# do.net
KiCad netlist of a schematic drawn in Altium Designer
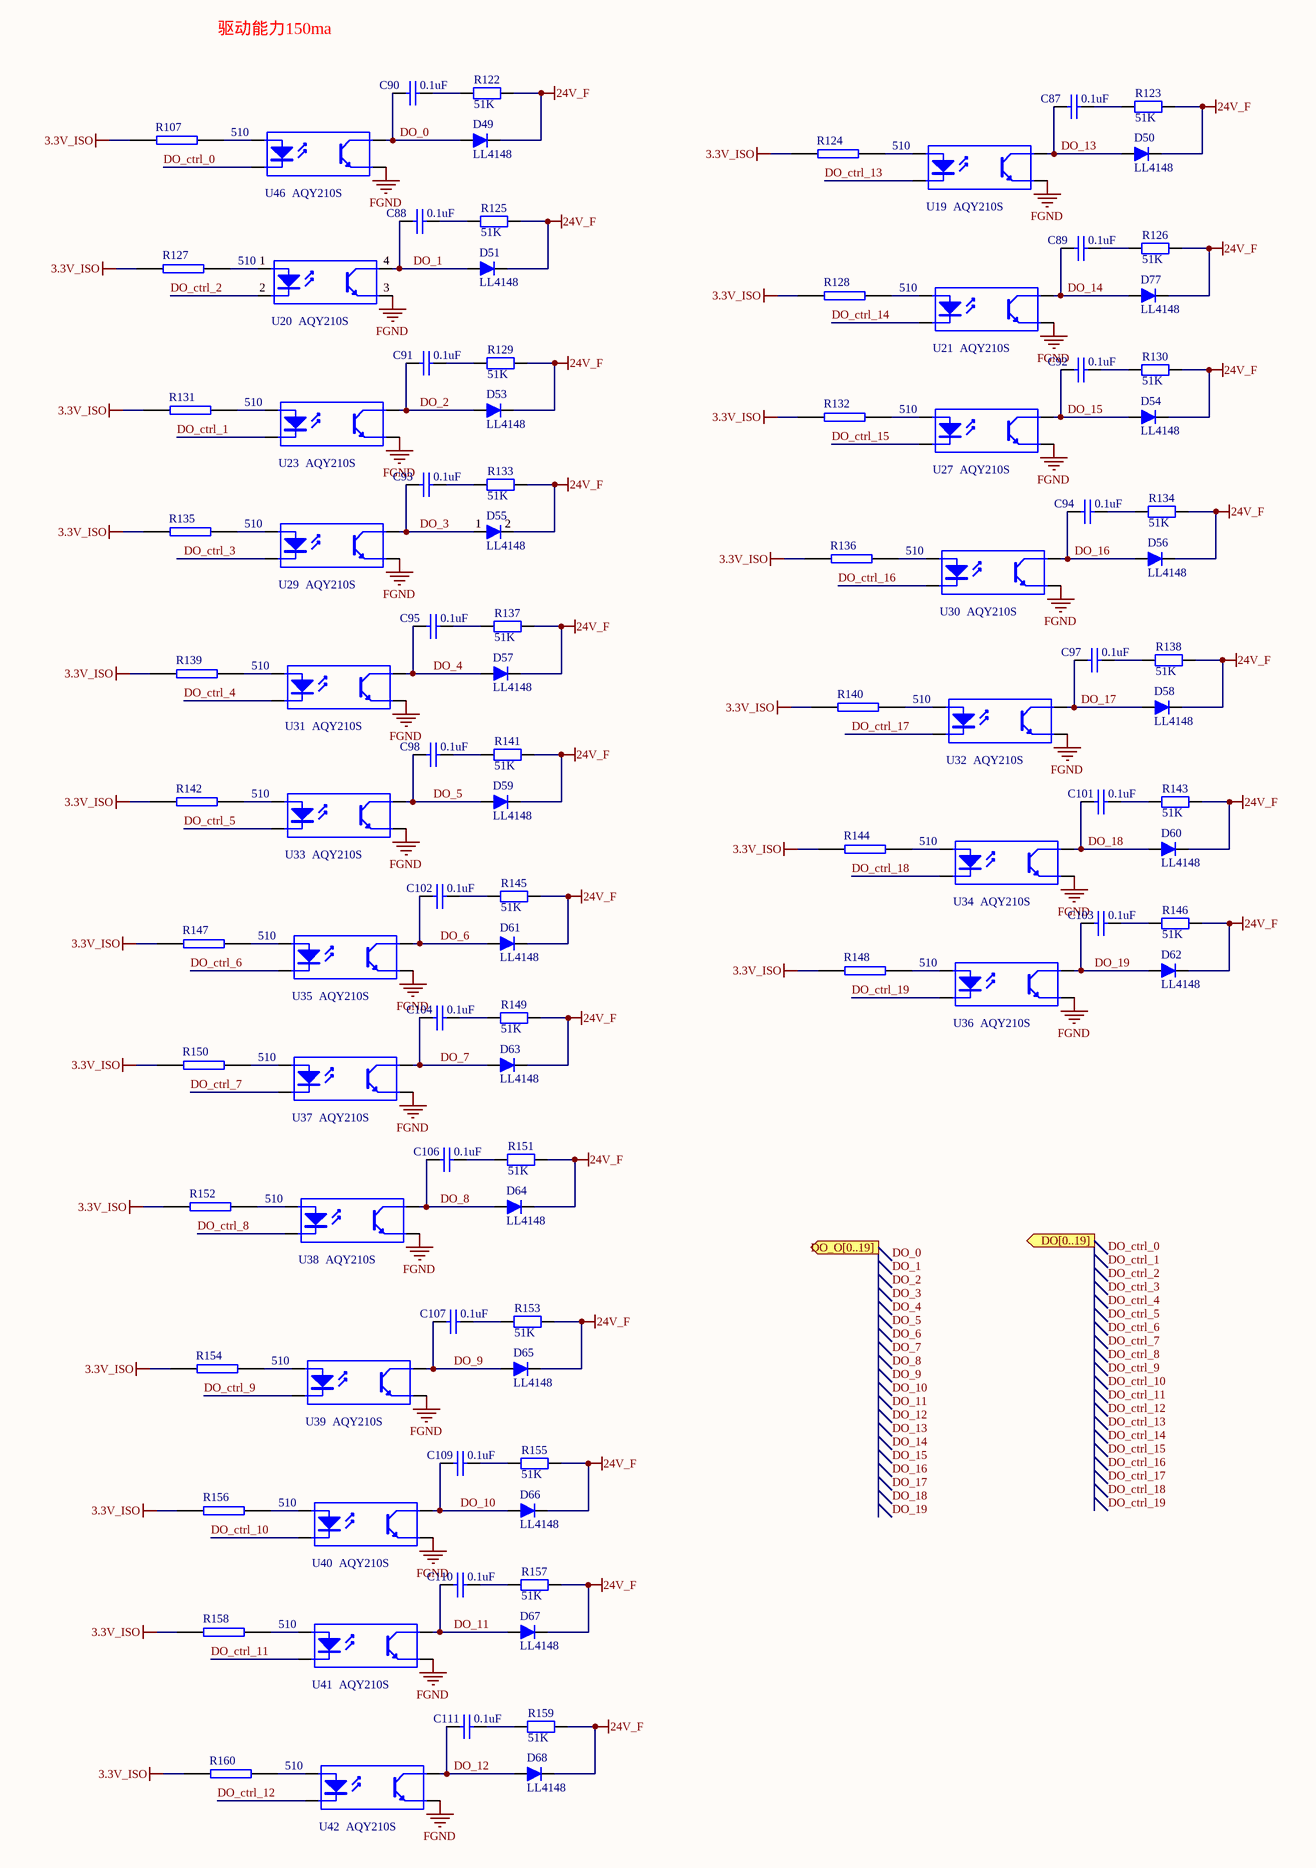
[diagram p0: do.SchDoc]

(export (version "E")
  (design (tool "Eeschema 10.0.6"))
  (components
    (comp (ref "C87")
      (value "0.1uF")
      (footprint "0603C")
      (description "Capacitor")
      (libsource (lib "*") (part "CAP"))
    )
    (comp (ref "C88")
      (value "0.1uF")
      (footprint "0603C")
      (description "Capacitor")
      (libsource (lib "*") (part "CAP"))
    )
    (comp (ref "C89")
      (value "0.1uF")
      (footprint "0603C")
      (description "Capacitor")
      (libsource (lib "*") (part "CAP"))
    )
    (comp (ref "C90")
      (value "0.1uF")
      (footprint "0603C")
      (description "Capacitor")
      (libsource (lib "*") (part "CAP"))
    )
    (comp (ref "C91")
      (value "0.1uF")
      (footprint "0603C")
      (description "Capacitor")
      (libsource (lib "*") (part "CAP"))
    )
    (comp (ref "C92")
      (value "0.1uF")
      (footprint "0603C")
      (description "Capacitor")
      (libsource (lib "*") (part "CAP"))
    )
    (comp (ref "C93")
      (value "0.1uF")
      (footprint "0603C")
      (description "Capacitor")
      (libsource (lib "*") (part "CAP"))
    )
    (comp (ref "C94")
      (value "0.1uF")
      (footprint "0603C")
      (description "Capacitor")
      (libsource (lib "*") (part "CAP"))
    )
    (comp (ref "C95")
      (value "0.1uF")
      (footprint "0603C")
      (description "Capacitor")
      (libsource (lib "*") (part "CAP"))
    )
    (comp (ref "C97")
      (value "0.1uF")
      (footprint "0603C")
      (description "Capacitor")
      (libsource (lib "*") (part "CAP"))
    )
    (comp (ref "C98")
      (value "0.1uF")
      (footprint "0603C")
      (description "Capacitor")
      (libsource (lib "*") (part "CAP"))
    )
    (comp (ref "C101")
      (value "0.1uF")
      (footprint "0603C")
      (description "Capacitor")
      (libsource (lib "*") (part "CAP"))
    )
    (comp (ref "C102")
      (value "0.1uF")
      (footprint "0603C")
      (description "Capacitor")
      (libsource (lib "*") (part "CAP"))
    )
    (comp (ref "C103")
      (value "0.1uF")
      (footprint "0603C")
      (description "Capacitor")
      (libsource (lib "*") (part "CAP"))
    )
    (comp (ref "C104")
      (value "0.1uF")
      (footprint "0603C")
      (description "Capacitor")
      (libsource (lib "*") (part "CAP"))
    )
    (comp (ref "C106")
      (value "0.1uF")
      (footprint "0603C")
      (description "Capacitor")
      (libsource (lib "*") (part "CAP"))
    )
    (comp (ref "C107")
      (value "0.1uF")
      (footprint "0603C")
      (description "Capacitor")
      (libsource (lib "*") (part "CAP"))
    )
    (comp (ref "C109")
      (value "0.1uF")
      (footprint "0603C")
      (description "Capacitor")
      (libsource (lib "*") (part "CAP"))
    )
    (comp (ref "C110")
      (value "0.1uF")
      (footprint "0603C")
      (description "Capacitor")
      (libsource (lib "*") (part "CAP"))
    )
    (comp (ref "C111")
      (value "0.1uF")
      (footprint "0603C")
      (description "Capacitor")
      (libsource (lib "*") (part "CAP"))
    )
    (comp (ref "D49")
      (value "LL4148")
      (footprint "DO-213AB/LL34/MiniMELF")
      (description "VISHAY,LL4148,圆柱体MiniMELF100V/2A,ROHS")
      (libsource (lib "controller_V1.1") (part "LL4148"))
    )
    (comp (ref "D50")
      (value "LL4148")
      (footprint "DO-213AB/LL34/MiniMELF")
      (description "VISHAY,LL4148,圆柱体MiniMELF100V/2A,ROHS")
      (libsource (lib "controller_V1.1") (part "LL4148"))
    )
    (comp (ref "D51")
      (value "LL4148")
      (footprint "DO-213AB/LL34/MiniMELF")
      (description "VISHAY,LL4148,圆柱体MiniMELF100V/2A,ROHS")
      (libsource (lib "controller_V1.1") (part "LL4148"))
    )
    (comp (ref "D53")
      (value "LL4148")
      (footprint "DO-213AB/LL34/MiniMELF")
      (description "VISHAY,LL4148,圆柱体MiniMELF100V/2A,ROHS")
      (libsource (lib "controller_V1.1") (part "LL4148"))
    )
    (comp (ref "D54")
      (value "LL4148")
      (footprint "DO-213AB/LL34/MiniMELF")
      (description "VISHAY,LL4148,圆柱体MiniMELF100V/2A,ROHS")
      (libsource (lib "controller_V1.1") (part "LL4148"))
    )
    (comp (ref "D55")
      (value "LL4148")
      (footprint "DO-213AB/LL34/MiniMELF")
      (description "VISHAY,LL4148,圆柱体MiniMELF100V/2A,ROHS")
      (libsource (lib "") (part "LL4148_1"))
    )
    (comp (ref "D56")
      (value "LL4148")
      (footprint "DO-213AB/LL34/MiniMELF")
      (description "VISHAY,LL4148,圆柱体MiniMELF100V/2A,ROHS")
      (libsource (lib "controller_V1.1") (part "LL4148"))
    )
    (comp (ref "D57")
      (value "LL4148")
      (footprint "DO-213AB/LL34/MiniMELF")
      (description "VISHAY,LL4148,圆柱体MiniMELF100V/2A,ROHS")
      (libsource (lib "controller_V1.1") (part "LL4148"))
    )
    (comp (ref "D58")
      (value "LL4148")
      (footprint "DO-213AB/LL34/MiniMELF")
      (description "VISHAY,LL4148,圆柱体MiniMELF100V/2A,ROHS")
      (libsource (lib "controller_V1.1") (part "LL4148"))
    )
    (comp (ref "D59")
      (value "LL4148")
      (footprint "DO-213AB/LL34/MiniMELF")
      (description "VISHAY,LL4148,圆柱体MiniMELF100V/2A,ROHS")
      (libsource (lib "controller_V1.1") (part "LL4148"))
    )
    (comp (ref "D60")
      (value "LL4148")
      (footprint "DO-213AB/LL34/MiniMELF")
      (description "VISHAY,LL4148,圆柱体MiniMELF100V/2A,ROHS")
      (libsource (lib "controller_V1.1") (part "LL4148"))
    )
    (comp (ref "D61")
      (value "LL4148")
      (footprint "DO-213AB/LL34/MiniMELF")
      (description "VISHAY,LL4148,圆柱体MiniMELF100V/2A,ROHS")
      (libsource (lib "controller_V1.1") (part "LL4148"))
    )
    (comp (ref "D62")
      (value "LL4148")
      (footprint "DO-213AB/LL34/MiniMELF")
      (description "VISHAY,LL4148,圆柱体MiniMELF100V/2A,ROHS")
      (libsource (lib "controller_V1.1") (part "LL4148"))
    )
    (comp (ref "D63")
      (value "LL4148")
      (footprint "DO-213AB/LL34/MiniMELF")
      (description "VISHAY,LL4148,圆柱体MiniMELF100V/2A,ROHS")
      (libsource (lib "controller_V1.1") (part "LL4148"))
    )
    (comp (ref "D64")
      (value "LL4148")
      (footprint "DO-213AB/LL34/MiniMELF")
      (description "VISHAY,LL4148,圆柱体MiniMELF100V/2A,ROHS")
      (libsource (lib "controller_V1.1") (part "LL4148"))
    )
    (comp (ref "D65")
      (value "LL4148")
      (footprint "DO-213AB/LL34/MiniMELF")
      (description "VISHAY,LL4148,圆柱体MiniMELF100V/2A,ROHS")
      (libsource (lib "controller_V1.1") (part "LL4148"))
    )
    (comp (ref "D66")
      (value "LL4148")
      (footprint "DO-213AB/LL34/MiniMELF")
      (description "VISHAY,LL4148,圆柱体MiniMELF100V/2A,ROHS")
      (libsource (lib "controller_V1.1") (part "LL4148"))
    )
    (comp (ref "D67")
      (value "LL4148")
      (footprint "DO-213AB/LL34/MiniMELF")
      (description "VISHAY,LL4148,圆柱体MiniMELF100V/2A,ROHS")
      (libsource (lib "controller_V1.1") (part "LL4148"))
    )
    (comp (ref "D68")
      (value "LL4148")
      (footprint "DO-213AB/LL34/MiniMELF")
      (description "VISHAY,LL4148,圆柱体MiniMELF100V/2A,ROHS")
      (libsource (lib "controller_V1.1") (part "LL4148"))
    )
    (comp (ref "D77")
      (value "LL4148")
      (footprint "DO-213AB/LL34/MiniMELF")
      (description "VISHAY,LL4148,圆柱体MiniMELF100V/2A,ROHS")
      (libsource (lib "controller_V1.1") (part "LL4148"))
    )
    (comp (ref "R107") (value "510") (footprint "0603R") (libsource (lib "*") (part "RES2")))
    (comp (ref "R122") (value "51K") (footprint "0603R") (libsource (lib "MQlibrary") (part "Res0805M")))
    (comp (ref "R123") (value "51K") (footprint "0603R") (libsource (lib "MQlibrary") (part "Res0805M")))
    (comp (ref "R124") (value "510") (footprint "0603R") (libsource (lib "*") (part "RES2")))
    (comp (ref "R125") (value "51K") (footprint "0603R") (libsource (lib "MQlibrary") (part "Res0805M")))
    (comp (ref "R126") (value "51K") (footprint "0603R") (libsource (lib "MQlibrary") (part "Res0805M")))
    (comp (ref "R127") (value "510") (footprint "0603R") (libsource (lib "*") (part "RES2")))
    (comp (ref "R128") (value "510") (footprint "0603R") (libsource (lib "*") (part "RES2")))
    (comp (ref "R129") (value "51K") (footprint "0603R") (libsource (lib "MQlibrary") (part "Res0805M")))
    (comp (ref "R130") (value "51K") (footprint "0603R") (libsource (lib "MQlibrary") (part "Res0805M")))
    (comp (ref "R131") (value "510") (footprint "0603R") (libsource (lib "*") (part "RES2")))
    (comp (ref "R132") (value "510") (footprint "0603R") (libsource (lib "*") (part "RES2")))
    (comp (ref "R133") (value "51K") (footprint "0603R") (libsource (lib "MQlibrary") (part "Res0805M")))
    (comp (ref "R134") (value "51K") (footprint "0603R") (libsource (lib "MQlibrary") (part "Res0805M")))
    (comp (ref "R135") (value "510") (footprint "0603R") (libsource (lib "*") (part "RES2")))
    (comp (ref "R136") (value "510") (footprint "0603R") (libsource (lib "*") (part "RES2")))
    (comp (ref "R137") (value "51K") (footprint "0603R") (libsource (lib "MQlibrary") (part "Res0805M")))
    (comp (ref "R138") (value "51K") (footprint "0603R") (libsource (lib "MQlibrary") (part "Res0805M")))
    (comp (ref "R139") (value "510") (footprint "0603R") (libsource (lib "*") (part "RES2")))
    (comp (ref "R140") (value "510") (footprint "0603R") (libsource (lib "*") (part "RES2")))
    (comp (ref "R141") (value "51K") (footprint "0603R") (libsource (lib "MQlibrary") (part "Res0805M")))
    (comp (ref "R142") (value "510") (footprint "0603R") (libsource (lib "*") (part "RES2")))
    (comp (ref "R143") (value "51K") (footprint "0603R") (libsource (lib "MQlibrary") (part "Res0805M")))
    (comp (ref "R144") (value "510") (footprint "0603R") (libsource (lib "*") (part "RES2")))
    (comp (ref "R145") (value "51K") (footprint "0603R") (libsource (lib "MQlibrary") (part "Res0805M")))
    (comp (ref "R146") (value "51K") (footprint "0603R") (libsource (lib "MQlibrary") (part "Res0805M")))
    (comp (ref "R147") (value "510") (footprint "0603R") (libsource (lib "*") (part "RES2")))
    (comp (ref "R148") (value "510") (footprint "0603R") (libsource (lib "*") (part "RES2")))
    (comp (ref "R149") (value "51K") (footprint "0603R") (libsource (lib "MQlibrary") (part "Res0805M")))
    (comp (ref "R150") (value "510") (footprint "0603R") (libsource (lib "*") (part "RES2")))
    (comp (ref "R151") (value "51K") (footprint "0603R") (libsource (lib "MQlibrary") (part "Res0805M")))
    (comp (ref "R152") (value "510") (footprint "0603R") (libsource (lib "*") (part "RES2")))
    (comp (ref "R153") (value "51K") (footprint "0603R") (libsource (lib "MQlibrary") (part "Res0805M")))
    (comp (ref "R154") (value "510") (footprint "0603R") (libsource (lib "*") (part "RES2")))
    (comp (ref "R155") (value "51K") (footprint "0603R") (libsource (lib "MQlibrary") (part "Res0805M")))
    (comp (ref "R156") (value "510") (footprint "0603R") (libsource (lib "*") (part "RES2")))
    (comp (ref "R157") (value "51K") (footprint "0603R") (libsource (lib "MQlibrary") (part "Res0805M")))
    (comp (ref "R158") (value "510") (footprint "0603R") (libsource (lib "*") (part "RES2")))
    (comp (ref "R159") (value "51K") (footprint "0603R") (libsource (lib "MQlibrary") (part "Res0805M")))
    (comp (ref "R160") (value "510") (footprint "0603R") (libsource (lib "*") (part "RES2")))
    (comp (ref "U19")
      (value "AQY210S")
      (footprint "sop4")
      (description "4-Pin Phototransistor Optocoupler")
      (fields (field (name "PUBLISHER") "Altium Limited"))
      (libsource (lib "Miscellaneous Devices") (part "Optoisolator1"))
    )
    (comp (ref "U20")
      (value "AQY210S")
      (footprint "sop4")
      (description "4-Pin Phototransistor Optocoupler")
      (fields (field (name "PUBLISHER") "Altium Limited"))
      (libsource (lib "") (part "Optoisolator1_1"))
    )
    (comp (ref "U21")
      (value "AQY210S")
      (footprint "sop4")
      (description "4-Pin Phototransistor Optocoupler")
      (fields (field (name "PUBLISHER") "Altium Limited"))
      (libsource (lib "Miscellaneous Devices") (part "Optoisolator1"))
    )
    (comp (ref "U23")
      (value "AQY210S")
      (footprint "sop4")
      (description "4-Pin Phototransistor Optocoupler")
      (fields (field (name "PUBLISHER") "Altium Limited"))
      (libsource (lib "Miscellaneous Devices") (part "Optoisolator1"))
    )
    (comp (ref "U27")
      (value "AQY210S")
      (footprint "sop4")
      (description "4-Pin Phototransistor Optocoupler")
      (fields (field (name "PUBLISHER") "Altium Limited"))
      (libsource (lib "Miscellaneous Devices") (part "Optoisolator1"))
    )
    (comp (ref "U29")
      (value "AQY210S")
      (footprint "sop4")
      (description "4-Pin Phototransistor Optocoupler")
      (fields (field (name "PUBLISHER") "Altium Limited"))
      (libsource (lib "Miscellaneous Devices") (part "Optoisolator1"))
    )
    (comp (ref "U30")
      (value "AQY210S")
      (footprint "sop4")
      (description "4-Pin Phototransistor Optocoupler")
      (fields (field (name "PUBLISHER") "Altium Limited"))
      (libsource (lib "Miscellaneous Devices") (part "Optoisolator1"))
    )
    (comp (ref "U31")
      (value "AQY210S")
      (footprint "sop4")
      (description "4-Pin Phototransistor Optocoupler")
      (fields (field (name "PUBLISHER") "Altium Limited"))
      (libsource (lib "Miscellaneous Devices") (part "Optoisolator1"))
    )
    (comp (ref "U32")
      (value "AQY210S")
      (footprint "sop4")
      (description "4-Pin Phototransistor Optocoupler")
      (fields (field (name "PUBLISHER") "Altium Limited"))
      (libsource (lib "Miscellaneous Devices") (part "Optoisolator1"))
    )
    (comp (ref "U33")
      (value "AQY210S")
      (footprint "sop4")
      (description "4-Pin Phototransistor Optocoupler")
      (fields (field (name "PUBLISHER") "Altium Limited"))
      (libsource (lib "Miscellaneous Devices") (part "Optoisolator1"))
    )
    (comp (ref "U34")
      (value "AQY210S")
      (footprint "sop4")
      (description "4-Pin Phototransistor Optocoupler")
      (fields (field (name "PUBLISHER") "Altium Limited"))
      (libsource (lib "Miscellaneous Devices") (part "Optoisolator1"))
    )
    (comp (ref "U35")
      (value "AQY210S")
      (footprint "sop4")
      (description "4-Pin Phototransistor Optocoupler")
      (fields (field (name "PUBLISHER") "Altium Limited"))
      (libsource (lib "Miscellaneous Devices") (part "Optoisolator1"))
    )
    (comp (ref "U36")
      (value "AQY210S")
      (footprint "sop4")
      (description "4-Pin Phototransistor Optocoupler")
      (fields (field (name "PUBLISHER") "Altium Limited"))
      (libsource (lib "Miscellaneous Devices") (part "Optoisolator1"))
    )
    (comp (ref "U37")
      (value "AQY210S")
      (footprint "sop4")
      (description "4-Pin Phototransistor Optocoupler")
      (fields (field (name "PUBLISHER") "Altium Limited"))
      (libsource (lib "Miscellaneous Devices") (part "Optoisolator1"))
    )
    (comp (ref "U38")
      (value "AQY210S")
      (footprint "sop4")
      (description "4-Pin Phototransistor Optocoupler")
      (fields (field (name "PUBLISHER") "Altium Limited"))
      (libsource (lib "Miscellaneous Devices") (part "Optoisolator1"))
    )
    (comp (ref "U39")
      (value "AQY210S")
      (footprint "sop4")
      (description "4-Pin Phototransistor Optocoupler")
      (fields (field (name "PUBLISHER") "Altium Limited"))
      (libsource (lib "Miscellaneous Devices") (part "Optoisolator1"))
    )
    (comp (ref "U40")
      (value "AQY210S")
      (footprint "sop4")
      (description "4-Pin Phototransistor Optocoupler")
      (fields (field (name "PUBLISHER") "Altium Limited"))
      (libsource (lib "Miscellaneous Devices") (part "Optoisolator1"))
    )
    (comp (ref "U41")
      (value "AQY210S")
      (footprint "sop4")
      (description "4-Pin Phototransistor Optocoupler")
      (fields (field (name "PUBLISHER") "Altium Limited"))
      (libsource (lib "Miscellaneous Devices") (part "Optoisolator1"))
    )
    (comp (ref "U42")
      (value "AQY210S")
      (footprint "sop4")
      (description "4-Pin Phototransistor Optocoupler")
      (fields (field (name "PUBLISHER") "Altium Limited"))
      (libsource (lib "Miscellaneous Devices") (part "Optoisolator1"))
    )
    (comp (ref "U46")
      (value "AQY210S")
      (footprint "sop4")
      (description "4-Pin Phototransistor Optocoupler")
      (fields (field (name "PUBLISHER") "Altium Limited"))
      (libsource (lib "Miscellaneous Devices") (part "Optoisolator1"))
    )
  )
  (nets
    (net (code "42") (name "/DO_0") (class "Default")
      (node (ref "C90") (pin "1") (pinfunction "1_1") (pintype "passive"))
      (node (ref "D49") (pin "1") (pinfunction "A_1") (pintype "passive"))
      (node (ref "U46") (pin "4") (pinfunction "C_4") (pintype "passive"))
    )
    (net (code "43") (name "/DO_1") (class "Default")
      (node (ref "C88") (pin "1") (pinfunction "1_1") (pintype "passive"))
      (node (ref "D51") (pin "1") (pinfunction "A_1") (pintype "passive"))
      (node (ref "U20") (pin "4") (pinfunction "C_4") (pintype "passive"))
    )
    (net (code "44") (name "/DO_2") (class "Default")
      (node (ref "C91") (pin "1") (pinfunction "1_1") (pintype "passive"))
      (node (ref "D53") (pin "1") (pinfunction "A_1") (pintype "passive"))
      (node (ref "U23") (pin "4") (pinfunction "C_4") (pintype "passive"))
    )
    (net (code "45") (name "/DO_3") (class "Default")
      (node (ref "C93") (pin "1") (pinfunction "1_1") (pintype "passive"))
      (node (ref "D55") (pin "1") (pinfunction "A_1") (pintype "passive"))
      (node (ref "U29") (pin "4") (pinfunction "C_4") (pintype "passive"))
    )
    (net (code "46") (name "/DO_4") (class "Default")
      (node (ref "C95") (pin "1") (pinfunction "1_1") (pintype "passive"))
      (node (ref "D57") (pin "1") (pinfunction "A_1") (pintype "passive"))
      (node (ref "U31") (pin "4") (pinfunction "C_4") (pintype "passive"))
    )
    (net (code "47") (name "/DO_5") (class "Default")
      (node (ref "C98") (pin "1") (pinfunction "1_1") (pintype "passive"))
      (node (ref "D59") (pin "1") (pinfunction "A_1") (pintype "passive"))
      (node (ref "U33") (pin "4") (pinfunction "C_4") (pintype "passive"))
    )
    (net (code "48") (name "/DO_6") (class "Default")
      (node (ref "C102") (pin "1") (pinfunction "1_1") (pintype "passive"))
      (node (ref "D61") (pin "1") (pinfunction "A_1") (pintype "passive"))
      (node (ref "U35") (pin "4") (pinfunction "C_4") (pintype "passive"))
    )
    (net (code "49") (name "/DO_7") (class "Default")
      (node (ref "C104") (pin "1") (pinfunction "1_1") (pintype "passive"))
      (node (ref "D63") (pin "1") (pinfunction "A_1") (pintype "passive"))
      (node (ref "U37") (pin "4") (pinfunction "C_4") (pintype "passive"))
    )
    (net (code "50") (name "/DO_8") (class "Default")
      (node (ref "C106") (pin "1") (pinfunction "1_1") (pintype "passive"))
      (node (ref "D64") (pin "1") (pinfunction "A_1") (pintype "passive"))
      (node (ref "U38") (pin "4") (pinfunction "C_4") (pintype "passive"))
    )
    (net (code "51") (name "/DO_9") (class "Default")
      (node (ref "C107") (pin "1") (pinfunction "1_1") (pintype "passive"))
      (node (ref "D65") (pin "1") (pinfunction "A_1") (pintype "passive"))
      (node (ref "U39") (pin "4") (pinfunction "C_4") (pintype "passive"))
    )
    (net (code "52") (name "/DO_10") (class "Default")
      (node (ref "C109") (pin "1") (pinfunction "1_1") (pintype "passive"))
      (node (ref "D66") (pin "1") (pinfunction "A_1") (pintype "passive"))
      (node (ref "U40") (pin "4") (pinfunction "C_4") (pintype "passive"))
    )
    (net (code "53") (name "/DO_11") (class "Default")
      (node (ref "C110") (pin "1") (pinfunction "1_1") (pintype "passive"))
      (node (ref "D67") (pin "1") (pinfunction "A_1") (pintype "passive"))
      (node (ref "U41") (pin "4") (pinfunction "C_4") (pintype "passive"))
    )
    (net (code "54") (name "/DO_12") (class "Default")
      (node (ref "C111") (pin "1") (pinfunction "1_1") (pintype "passive"))
      (node (ref "D68") (pin "1") (pinfunction "A_1") (pintype "passive"))
      (node (ref "U42") (pin "4") (pinfunction "C_4") (pintype "passive"))
    )
    (net (code "55") (name "/DO_13") (class "Default")
      (node (ref "C87") (pin "1") (pinfunction "1_1") (pintype "passive"))
      (node (ref "D50") (pin "1") (pinfunction "A_1") (pintype "passive"))
      (node (ref "U19") (pin "4") (pinfunction "C_4") (pintype "passive"))
    )
    (net (code "56") (name "/DO_14") (class "Default")
      (node (ref "C89") (pin "1") (pinfunction "1_1") (pintype "passive"))
      (node (ref "D77") (pin "1") (pinfunction "A_1") (pintype "passive"))
      (node (ref "U21") (pin "4") (pinfunction "C_4") (pintype "passive"))
    )
    (net (code "57") (name "/DO_15") (class "Default")
      (node (ref "C92") (pin "1") (pinfunction "1_1") (pintype "passive"))
      (node (ref "D54") (pin "1") (pinfunction "A_1") (pintype "passive"))
      (node (ref "U27") (pin "4") (pinfunction "C_4") (pintype "passive"))
    )
    (net (code "58") (name "/DO_16") (class "Default")
      (node (ref "C94") (pin "1") (pinfunction "1_1") (pintype "passive"))
      (node (ref "D56") (pin "1") (pinfunction "A_1") (pintype "passive"))
      (node (ref "U30") (pin "4") (pinfunction "C_4") (pintype "passive"))
    )
    (net (code "59") (name "/DO_17") (class "Default")
      (node (ref "C97") (pin "1") (pinfunction "1_1") (pintype "passive"))
      (node (ref "D58") (pin "1") (pinfunction "A_1") (pintype "passive"))
      (node (ref "U32") (pin "4") (pinfunction "C_4") (pintype "passive"))
    )
    (net (code "60") (name "/DO_18") (class "Default")
      (node (ref "C101") (pin "1") (pinfunction "1_1") (pintype "passive"))
      (node (ref "D60") (pin "1") (pinfunction "A_1") (pintype "passive"))
      (node (ref "U34") (pin "4") (pinfunction "C_4") (pintype "passive"))
    )
    (net (code "61") (name "/DO_19") (class "Default")
      (node (ref "C103") (pin "1") (pinfunction "1_1") (pintype "passive"))
      (node (ref "D62") (pin "1") (pinfunction "A_1") (pintype "passive"))
      (node (ref "U36") (pin "4") (pinfunction "C_4") (pintype "passive"))
    )
    (net (code "63") (name "/DO_ctrl_0") (class "Default")
      (node (ref "U46") (pin "2") (pinfunction "K_2") (pintype "passive"))
    )
    (net (code "64") (name "/DO_ctrl_1") (class "Default")
      (node (ref "U23") (pin "2") (pinfunction "K_2") (pintype "passive"))
    )
    (net (code "65") (name "/DO_ctrl_2") (class "Default")
      (node (ref "U20") (pin "2") (pinfunction "K_2") (pintype "passive"))
    )
    (net (code "66") (name "/DO_ctrl_3") (class "Default")
      (node (ref "U29") (pin "2") (pinfunction "K_2") (pintype "passive"))
    )
    (net (code "67") (name "/DO_ctrl_4") (class "Default")
      (node (ref "U31") (pin "2") (pinfunction "K_2") (pintype "passive"))
    )
    (net (code "68") (name "/DO_ctrl_5") (class "Default")
      (node (ref "U33") (pin "2") (pinfunction "K_2") (pintype "passive"))
    )
    (net (code "69") (name "/DO_ctrl_6") (class "Default")
      (node (ref "U35") (pin "2") (pinfunction "K_2") (pintype "passive"))
    )
    (net (code "70") (name "/DO_ctrl_7") (class "Default")
      (node (ref "U37") (pin "2") (pinfunction "K_2") (pintype "passive"))
    )
    (net (code "71") (name "/DO_ctrl_8") (class "Default")
      (node (ref "U38") (pin "2") (pinfunction "K_2") (pintype "passive"))
    )
    (net (code "72") (name "/DO_ctrl_9") (class "Default")
      (node (ref "U39") (pin "2") (pinfunction "K_2") (pintype "passive"))
    )
    (net (code "73") (name "/DO_ctrl_10") (class "Default")
      (node (ref "U40") (pin "2") (pinfunction "K_2") (pintype "passive"))
    )
    (net (code "74") (name "/DO_ctrl_11") (class "Default")
      (node (ref "U41") (pin "2") (pinfunction "K_2") (pintype "passive"))
    )
    (net (code "75") (name "/DO_ctrl_12") (class "Default")
      (node (ref "U42") (pin "2") (pinfunction "K_2") (pintype "passive"))
    )
    (net (code "76") (name "/DO_ctrl_13") (class "Default")
      (node (ref "U19") (pin "2") (pinfunction "K_2") (pintype "passive"))
    )
    (net (code "77") (name "/DO_ctrl_14") (class "Default")
      (node (ref "U21") (pin "2") (pinfunction "K_2") (pintype "passive"))
    )
    (net (code "78") (name "/DO_ctrl_15") (class "Default")
      (node (ref "U27") (pin "2") (pinfunction "K_2") (pintype "passive"))
    )
    (net (code "79") (name "/DO_ctrl_16") (class "Default")
      (node (ref "U30") (pin "2") (pinfunction "K_2") (pintype "passive"))
    )
    (net (code "80") (name "/DO_ctrl_17") (class "Default")
      (node (ref "U32") (pin "2") (pinfunction "K_2") (pintype "passive"))
    )
    (net (code "81") (name "/DO_ctrl_18") (class "Default")
      (node (ref "U34") (pin "2") (pinfunction "K_2") (pintype "passive"))
    )
    (net (code "82") (name "/DO_ctrl_19") (class "Default")
      (node (ref "U36") (pin "2") (pinfunction "K_2") (pintype "passive"))
    )
    (net (code "83") (name "3.3V_ISO") (class "Default")
      (node (ref "R107") (pin "2") (pinfunction "2_2") (pintype "passive"))
      (node (ref "R124") (pin "2") (pinfunction "2_2") (pintype "passive"))
      (node (ref "R127") (pin "2") (pinfunction "2_2") (pintype "passive"))
      (node (ref "R128") (pin "2") (pinfunction "2_2") (pintype "passive"))
      (node (ref "R131") (pin "2") (pinfunction "2_2") (pintype "passive"))
      (node (ref "R132") (pin "2") (pinfunction "2_2") (pintype "passive"))
      (node (ref "R135") (pin "2") (pinfunction "2_2") (pintype "passive"))
      (node (ref "R136") (pin "2") (pinfunction "2_2") (pintype "passive"))
      (node (ref "R139") (pin "2") (pinfunction "2_2") (pintype "passive"))
      (node (ref "R140") (pin "2") (pinfunction "2_2") (pintype "passive"))
      (node (ref "R142") (pin "2") (pinfunction "2_2") (pintype "passive"))
      (node (ref "R144") (pin "2") (pinfunction "2_2") (pintype "passive"))
      (node (ref "R147") (pin "2") (pinfunction "2_2") (pintype "passive"))
      (node (ref "R148") (pin "2") (pinfunction "2_2") (pintype "passive"))
      (node (ref "R150") (pin "2") (pinfunction "2_2") (pintype "passive"))
      (node (ref "R152") (pin "2") (pinfunction "2_2") (pintype "passive"))
      (node (ref "R154") (pin "2") (pinfunction "2_2") (pintype "passive"))
      (node (ref "R156") (pin "2") (pinfunction "2_2") (pintype "passive"))
      (node (ref "R158") (pin "2") (pinfunction "2_2") (pintype "passive"))
      (node (ref "R160") (pin "2") (pinfunction "2_2") (pintype "passive"))
    )
    (net (code "84") (name "24V_F") (class "Default")
      (node (ref "D49") (pin "2") (pinfunction "K_2") (pintype "passive"))
      (node (ref "D50") (pin "2") (pinfunction "K_2") (pintype "passive"))
      (node (ref "D51") (pin "2") (pinfunction "K_2") (pintype "passive"))
      (node (ref "D53") (pin "2") (pinfunction "K_2") (pintype "passive"))
      (node (ref "D54") (pin "2") (pinfunction "K_2") (pintype "passive"))
      (node (ref "D55") (pin "2") (pinfunction "K_2") (pintype "passive"))
      (node (ref "D56") (pin "2") (pinfunction "K_2") (pintype "passive"))
      (node (ref "D57") (pin "2") (pinfunction "K_2") (pintype "passive"))
      (node (ref "D58") (pin "2") (pinfunction "K_2") (pintype "passive"))
      (node (ref "D59") (pin "2") (pinfunction "K_2") (pintype "passive"))
      (node (ref "D60") (pin "2") (pinfunction "K_2") (pintype "passive"))
      (node (ref "D61") (pin "2") (pinfunction "K_2") (pintype "passive"))
      (node (ref "D62") (pin "2") (pinfunction "K_2") (pintype "passive"))
      (node (ref "D63") (pin "2") (pinfunction "K_2") (pintype "passive"))
      (node (ref "D64") (pin "2") (pinfunction "K_2") (pintype "passive"))
      (node (ref "D65") (pin "2") (pinfunction "K_2") (pintype "passive"))
      (node (ref "D66") (pin "2") (pinfunction "K_2") (pintype "passive"))
      (node (ref "D67") (pin "2") (pinfunction "K_2") (pintype "passive"))
      (node (ref "D68") (pin "2") (pinfunction "K_2") (pintype "passive"))
      (node (ref "D77") (pin "2") (pinfunction "K_2") (pintype "passive"))
      (node (ref "R122") (pin "2") (pinfunction "2_2") (pintype "passive"))
      (node (ref "R123") (pin "2") (pinfunction "2_2") (pintype "passive"))
      (node (ref "R125") (pin "2") (pinfunction "2_2") (pintype "passive"))
      (node (ref "R126") (pin "2") (pinfunction "2_2") (pintype "passive"))
      (node (ref "R129") (pin "2") (pinfunction "2_2") (pintype "passive"))
      (node (ref "R130") (pin "2") (pinfunction "2_2") (pintype "passive"))
      (node (ref "R133") (pin "2") (pinfunction "2_2") (pintype "passive"))
      (node (ref "R134") (pin "2") (pinfunction "2_2") (pintype "passive"))
      (node (ref "R137") (pin "2") (pinfunction "2_2") (pintype "passive"))
      (node (ref "R138") (pin "2") (pinfunction "2_2") (pintype "passive"))
      (node (ref "R141") (pin "2") (pinfunction "2_2") (pintype "passive"))
      (node (ref "R143") (pin "2") (pinfunction "2_2") (pintype "passive"))
      (node (ref "R145") (pin "2") (pinfunction "2_2") (pintype "passive"))
      (node (ref "R146") (pin "2") (pinfunction "2_2") (pintype "passive"))
      (node (ref "R149") (pin "2") (pinfunction "2_2") (pintype "passive"))
      (node (ref "R151") (pin "2") (pinfunction "2_2") (pintype "passive"))
      (node (ref "R153") (pin "2") (pinfunction "2_2") (pintype "passive"))
      (node (ref "R155") (pin "2") (pinfunction "2_2") (pintype "passive"))
      (node (ref "R157") (pin "2") (pinfunction "2_2") (pintype "passive"))
      (node (ref "R159") (pin "2") (pinfunction "2_2") (pintype "passive"))
    )
    (net (code "85") (name "FGND") (class "Default")
      (node (ref "U19") (pin "3") (pinfunction "E_3") (pintype "passive"))
      (node (ref "U20") (pin "3") (pinfunction "E_3") (pintype "passive"))
      (node (ref "U21") (pin "3") (pinfunction "E_3") (pintype "passive"))
      (node (ref "U23") (pin "3") (pinfunction "E_3") (pintype "passive"))
      (node (ref "U27") (pin "3") (pinfunction "E_3") (pintype "passive"))
      (node (ref "U29") (pin "3") (pinfunction "E_3") (pintype "passive"))
      (node (ref "U30") (pin "3") (pinfunction "E_3") (pintype "passive"))
      (node (ref "U31") (pin "3") (pinfunction "E_3") (pintype "passive"))
      (node (ref "U32") (pin "3") (pinfunction "E_3") (pintype "passive"))
      (node (ref "U33") (pin "3") (pinfunction "E_3") (pintype "passive"))
      (node (ref "U34") (pin "3") (pinfunction "E_3") (pintype "passive"))
      (node (ref "U35") (pin "3") (pinfunction "E_3") (pintype "passive"))
      (node (ref "U36") (pin "3") (pinfunction "E_3") (pintype "passive"))
      (node (ref "U37") (pin "3") (pinfunction "E_3") (pintype "passive"))
      (node (ref "U38") (pin "3") (pinfunction "E_3") (pintype "passive"))
      (node (ref "U39") (pin "3") (pinfunction "E_3") (pintype "passive"))
      (node (ref "U40") (pin "3") (pinfunction "E_3") (pintype "passive"))
      (node (ref "U41") (pin "3") (pinfunction "E_3") (pintype "passive"))
      (node (ref "U42") (pin "3") (pinfunction "E_3") (pintype "passive"))
      (node (ref "U46") (pin "3") (pinfunction "E_3") (pintype "passive"))
    )
    (net (code "86") (name "Net-(C87-Pad2)") (class "Default")
      (node (ref "C87") (pin "2") (pinfunction "2_2") (pintype "passive"))
      (node (ref "R123") (pin "1") (pinfunction "1_1") (pintype "passive"))
    )
    (net (code "87") (name "Net-(C88-Pad2)") (class "Default")
      (node (ref "C88") (pin "2") (pinfunction "2_2") (pintype "passive"))
      (node (ref "R125") (pin "1") (pinfunction "1_1") (pintype "passive"))
    )
    (net (code "88") (name "Net-(C89-Pad2)") (class "Default")
      (node (ref "C89") (pin "2") (pinfunction "2_2") (pintype "passive"))
      (node (ref "R126") (pin "1") (pinfunction "1_1") (pintype "passive"))
    )
    (net (code "89") (name "Net-(C90-Pad2)") (class "Default")
      (node (ref "C90") (pin "2") (pinfunction "2_2") (pintype "passive"))
      (node (ref "R122") (pin "1") (pinfunction "1_1") (pintype "passive"))
    )
    (net (code "90") (name "Net-(C91-Pad2)") (class "Default")
      (node (ref "C91") (pin "2") (pinfunction "2_2") (pintype "passive"))
      (node (ref "R129") (pin "1") (pinfunction "1_1") (pintype "passive"))
    )
    (net (code "91") (name "Net-(C92-Pad2)") (class "Default")
      (node (ref "C92") (pin "2") (pinfunction "2_2") (pintype "passive"))
      (node (ref "R130") (pin "1") (pinfunction "1_1") (pintype "passive"))
    )
    (net (code "92") (name "Net-(C93-Pad2)") (class "Default")
      (node (ref "C93") (pin "2") (pinfunction "2_2") (pintype "passive"))
      (node (ref "R133") (pin "1") (pinfunction "1_1") (pintype "passive"))
    )
    (net (code "93") (name "Net-(C94-Pad2)") (class "Default")
      (node (ref "C94") (pin "2") (pinfunction "2_2") (pintype "passive"))
      (node (ref "R134") (pin "1") (pinfunction "1_1") (pintype "passive"))
    )
    (net (code "94") (name "Net-(C95-Pad2)") (class "Default")
      (node (ref "C95") (pin "2") (pinfunction "2_2") (pintype "passive"))
      (node (ref "R137") (pin "1") (pinfunction "1_1") (pintype "passive"))
    )
    (net (code "95") (name "Net-(C97-Pad2)") (class "Default")
      (node (ref "C97") (pin "2") (pinfunction "2_2") (pintype "passive"))
      (node (ref "R138") (pin "1") (pinfunction "1_1") (pintype "passive"))
    )
    (net (code "96") (name "Net-(C98-Pad2)") (class "Default")
      (node (ref "C98") (pin "2") (pinfunction "2_2") (pintype "passive"))
      (node (ref "R141") (pin "1") (pinfunction "1_1") (pintype "passive"))
    )
    (net (code "97") (name "Net-(C101-Pad2)") (class "Default")
      (node (ref "C101") (pin "2") (pinfunction "2_2") (pintype "passive"))
      (node (ref "R143") (pin "1") (pinfunction "1_1") (pintype "passive"))
    )
    (net (code "98") (name "Net-(C102-Pad2)") (class "Default")
      (node (ref "C102") (pin "2") (pinfunction "2_2") (pintype "passive"))
      (node (ref "R145") (pin "1") (pinfunction "1_1") (pintype "passive"))
    )
    (net (code "99") (name "Net-(C103-Pad2)") (class "Default")
      (node (ref "C103") (pin "2") (pinfunction "2_2") (pintype "passive"))
      (node (ref "R146") (pin "1") (pinfunction "1_1") (pintype "passive"))
    )
    (net (code "100") (name "Net-(C104-Pad2)") (class "Default")
      (node (ref "C104") (pin "2") (pinfunction "2_2") (pintype "passive"))
      (node (ref "R149") (pin "1") (pinfunction "1_1") (pintype "passive"))
    )
    (net (code "101") (name "Net-(C106-Pad2)") (class "Default")
      (node (ref "C106") (pin "2") (pinfunction "2_2") (pintype "passive"))
      (node (ref "R151") (pin "1") (pinfunction "1_1") (pintype "passive"))
    )
    (net (code "102") (name "Net-(C107-Pad2)") (class "Default")
      (node (ref "C107") (pin "2") (pinfunction "2_2") (pintype "passive"))
      (node (ref "R153") (pin "1") (pinfunction "1_1") (pintype "passive"))
    )
    (net (code "103") (name "Net-(C109-Pad2)") (class "Default")
      (node (ref "C109") (pin "2") (pinfunction "2_2") (pintype "passive"))
      (node (ref "R155") (pin "1") (pinfunction "1_1") (pintype "passive"))
    )
    (net (code "104") (name "Net-(C110-Pad2)") (class "Default")
      (node (ref "C110") (pin "2") (pinfunction "2_2") (pintype "passive"))
      (node (ref "R157") (pin "1") (pinfunction "1_1") (pintype "passive"))
    )
    (net (code "105") (name "Net-(C111-Pad2)") (class "Default")
      (node (ref "C111") (pin "2") (pinfunction "2_2") (pintype "passive"))
      (node (ref "R159") (pin "1") (pinfunction "1_1") (pintype "passive"))
    )
    (net (code "106") (name "Net-(U19-A)") (class "Default")
      (node (ref "R124") (pin "1") (pinfunction "1_1") (pintype "passive"))
      (node (ref "U19") (pin "1") (pinfunction "A_1") (pintype "passive"))
    )
    (net (code "107") (name "Net-(U20-A)") (class "Default")
      (node (ref "R127") (pin "1") (pinfunction "1_1") (pintype "passive"))
      (node (ref "U20") (pin "1") (pinfunction "A_1") (pintype "passive"))
    )
    (net (code "108") (name "Net-(U21-A)") (class "Default")
      (node (ref "R128") (pin "1") (pinfunction "1_1") (pintype "passive"))
      (node (ref "U21") (pin "1") (pinfunction "A_1") (pintype "passive"))
    )
    (net (code "109") (name "Net-(U23-A)") (class "Default")
      (node (ref "R131") (pin "1") (pinfunction "1_1") (pintype "passive"))
      (node (ref "U23") (pin "1") (pinfunction "A_1") (pintype "passive"))
    )
    (net (code "110") (name "Net-(U27-A)") (class "Default")
      (node (ref "R132") (pin "1") (pinfunction "1_1") (pintype "passive"))
      (node (ref "U27") (pin "1") (pinfunction "A_1") (pintype "passive"))
    )
    (net (code "111") (name "Net-(U29-A)") (class "Default")
      (node (ref "R135") (pin "1") (pinfunction "1_1") (pintype "passive"))
      (node (ref "U29") (pin "1") (pinfunction "A_1") (pintype "passive"))
    )
    (net (code "112") (name "Net-(U30-A)") (class "Default")
      (node (ref "R136") (pin "1") (pinfunction "1_1") (pintype "passive"))
      (node (ref "U30") (pin "1") (pinfunction "A_1") (pintype "passive"))
    )
    (net (code "113") (name "Net-(U31-A)") (class "Default")
      (node (ref "R139") (pin "1") (pinfunction "1_1") (pintype "passive"))
      (node (ref "U31") (pin "1") (pinfunction "A_1") (pintype "passive"))
    )
    (net (code "114") (name "Net-(U32-A)") (class "Default")
      (node (ref "R140") (pin "1") (pinfunction "1_1") (pintype "passive"))
      (node (ref "U32") (pin "1") (pinfunction "A_1") (pintype "passive"))
    )
    (net (code "115") (name "Net-(U33-A)") (class "Default")
      (node (ref "R142") (pin "1") (pinfunction "1_1") (pintype "passive"))
      (node (ref "U33") (pin "1") (pinfunction "A_1") (pintype "passive"))
    )
    (net (code "116") (name "Net-(U34-A)") (class "Default")
      (node (ref "R144") (pin "1") (pinfunction "1_1") (pintype "passive"))
      (node (ref "U34") (pin "1") (pinfunction "A_1") (pintype "passive"))
    )
    (net (code "117") (name "Net-(U35-A)") (class "Default")
      (node (ref "R147") (pin "1") (pinfunction "1_1") (pintype "passive"))
      (node (ref "U35") (pin "1") (pinfunction "A_1") (pintype "passive"))
    )
    (net (code "118") (name "Net-(U36-A)") (class "Default")
      (node (ref "R148") (pin "1") (pinfunction "1_1") (pintype "passive"))
      (node (ref "U36") (pin "1") (pinfunction "A_1") (pintype "passive"))
    )
    (net (code "119") (name "Net-(U37-A)") (class "Default")
      (node (ref "R150") (pin "1") (pinfunction "1_1") (pintype "passive"))
      (node (ref "U37") (pin "1") (pinfunction "A_1") (pintype "passive"))
    )
    (net (code "120") (name "Net-(U38-A)") (class "Default")
      (node (ref "R152") (pin "1") (pinfunction "1_1") (pintype "passive"))
      (node (ref "U38") (pin "1") (pinfunction "A_1") (pintype "passive"))
    )
    (net (code "121") (name "Net-(U39-A)") (class "Default")
      (node (ref "R154") (pin "1") (pinfunction "1_1") (pintype "passive"))
      (node (ref "U39") (pin "1") (pinfunction "A_1") (pintype "passive"))
    )
    (net (code "122") (name "Net-(U40-A)") (class "Default")
      (node (ref "R156") (pin "1") (pinfunction "1_1") (pintype "passive"))
      (node (ref "U40") (pin "1") (pinfunction "A_1") (pintype "passive"))
    )
    (net (code "123") (name "Net-(U41-A)") (class "Default")
      (node (ref "R158") (pin "1") (pinfunction "1_1") (pintype "passive"))
      (node (ref "U41") (pin "1") (pinfunction "A_1") (pintype "passive"))
    )
    (net (code "124") (name "Net-(U42-A)") (class "Default")
      (node (ref "R160") (pin "1") (pinfunction "1_1") (pintype "passive"))
      (node (ref "U42") (pin "1") (pinfunction "A_1") (pintype "passive"))
    )
    (net (code "125") (name "Net-(U46-A)") (class "Default")
      (node (ref "R107") (pin "1") (pinfunction "1_1") (pintype "passive"))
      (node (ref "U46") (pin "1") (pinfunction "A_1") (pintype "passive"))
    )
  )
)
